# 6x7.net
KiCad netlist of a schematic drawn in EAGLE
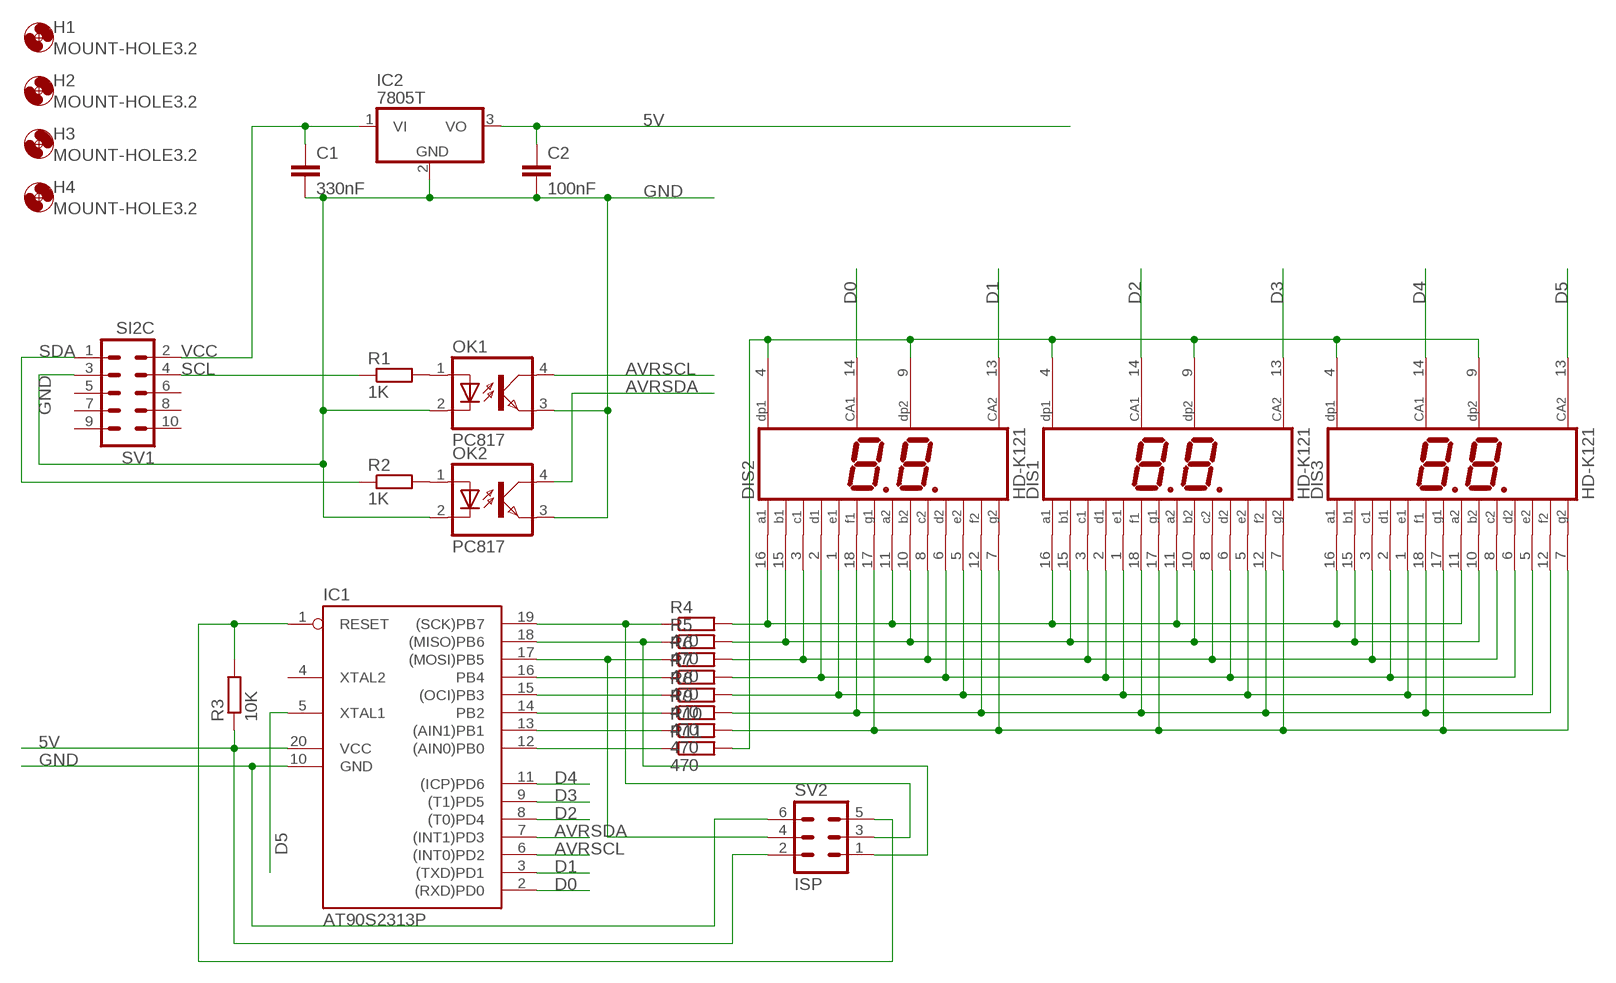
[diagram p0: schematic, sheet 1]

(export (version "E")
  (design (tool "Eeschema 10.0.6"))
  (components
    (comp (ref "C1")
      (value "330nF")
      (footprint "eagle-import:C2.5-3")
      (libsource (lib "eagle-import") (part "C2,5-3"))
    )
    (comp (ref "C2")
      (value "100nF")
      (footprint "eagle-import:C050-024X044")
      (libsource (lib "eagle-import") (part "C-EU050-024X044"))
    )
    (comp (ref "DIS1")
      (value "HD-K121")
      (footprint "eagle-import:HDSP-R")
      (libsource (lib "eagle-import") (part "HD-K121"))
    )
    (comp (ref "DIS2")
      (value "HD-K121")
      (footprint "eagle-import:HDSP-R")
      (libsource (lib "eagle-import") (part "HD-K121"))
    )
    (comp (ref "DIS3")
      (value "HD-K121")
      (footprint "eagle-import:HDSP-R")
      (libsource (lib "eagle-import") (part "HD-K121"))
    )
    (comp (ref "H1")
      (value "MOUNT-HOLE3.2")
      (footprint "eagle-import:3,2")
      (libsource (lib "eagle-import") (part "MOUNT-HOLE3.2"))
    )
    (comp (ref "H2")
      (value "MOUNT-HOLE3.2")
      (footprint "eagle-import:3,2")
      (libsource (lib "eagle-import") (part "MOUNT-HOLE3.2"))
    )
    (comp (ref "H3")
      (value "MOUNT-HOLE3.2")
      (footprint "eagle-import:3,2")
      (libsource (lib "eagle-import") (part "MOUNT-HOLE3.2"))
    )
    (comp (ref "H4")
      (value "MOUNT-HOLE3.2")
      (footprint "eagle-import:3,2")
      (libsource (lib "eagle-import") (part "MOUNT-HOLE3.2"))
    )
    (comp (ref "IC1")
      (value "AT90S2313P")
      (footprint "eagle-import:DIL20")
      (libsource (lib "eagle-import") (part "AT90S2313P"))
    )
    (comp (ref "IC2")
      (value "7805T")
      (footprint "eagle-import:TO220H")
      (libsource (lib "eagle-import") (part "78T05"))
    )
    (comp (ref "OK1")
      (value "PC817")
      (footprint "eagle-import:DIL04")
      (fields (field (name "MPN") "PC817X4J000F"))
      (libsource (lib "eagle-import") (part "PC817"))
    )
    (comp (ref "OK2")
      (value "PC817")
      (footprint "eagle-import:DIL04")
      (fields (field (name "MPN") "PC817X4J000F"))
      (libsource (lib "eagle-import") (part "PC817"))
    )
    (comp (ref "R1")
      (value "1K")
      (footprint "eagle-import:0207_10")
      (libsource (lib "eagle-import") (part "R-EU_0207/10"))
    )
    (comp (ref "R2")
      (value "1K")
      (footprint "eagle-import:0207_10")
      (libsource (lib "eagle-import") (part "R-EU_0207/10"))
    )
    (comp (ref "R3")
      (value "10K")
      (footprint "eagle-import:0207_10")
      (libsource (lib "eagle-import") (part "R-EU_0207/10"))
    )
    (comp (ref "R4")
      (value "470")
      (footprint "eagle-import:0207_10")
      (libsource (lib "eagle-import") (part "R-EU_0207/10"))
    )
    (comp (ref "R5")
      (value "470")
      (footprint "eagle-import:0207_10")
      (libsource (lib "eagle-import") (part "R-EU_0207/10"))
    )
    (comp (ref "R6")
      (value "470")
      (footprint "eagle-import:0207_10")
      (libsource (lib "eagle-import") (part "R-EU_0207/10"))
    )
    (comp (ref "R7")
      (value "470")
      (footprint "eagle-import:0207_10")
      (libsource (lib "eagle-import") (part "R-EU_0207/10"))
    )
    (comp (ref "R8")
      (value "470")
      (footprint "eagle-import:0207_10")
      (libsource (lib "eagle-import") (part "R-EU_0207/10"))
    )
    (comp (ref "R9")
      (value "470")
      (footprint "eagle-import:0207_10")
      (libsource (lib "eagle-import") (part "R-EU_0207/10"))
    )
    (comp (ref "R10")
      (value "470")
      (footprint "eagle-import:0207_10")
      (libsource (lib "eagle-import") (part "R-EU_0207/10"))
    )
    (comp (ref "R11")
      (value "470")
      (footprint "eagle-import:0207_10")
      (libsource (lib "eagle-import") (part "R-EU_0207/10"))
    )
    (comp (ref "SV1")
      (value "SI2C")
      (footprint "eagle-import:ML10")
      (libsource (lib "eagle-import") (part "ML10"))
    )
    (comp (ref "SV2")
      (value "ISP")
      (footprint "eagle-import:ML6")
      (libsource (lib "eagle-import") (part "ML6"))
    )
  )
  (nets
    (net (code "1") (name "/5V") (class "Default")
      (node (ref "C2") (pin "1") (pinfunction "1_1") (pintype "passive"))
      (node (ref "IC1") (pin "20") (pinfunction "VCC_20") (pintype "power_in"))
      (node (ref "IC2") (pin "3") (pinfunction "VO_3") (pintype "passive"))
      (node (ref "R3") (pin "1") (pinfunction "1_1") (pintype "passive"))
      (node (ref "SV2") (pin "2") (pinfunction "2_2") (pintype "passive"))
    )
    (net (code "2") (name "/AVRSCL") (class "Default")
      (node (ref "IC1") (pin "6") (pinfunction "(INT0)PD2_6") (pintype "bidirectional"))
      (node (ref "OK1") (pin "4") (pinfunction "COL_4") (pintype "passive"))
    )
    (net (code "3") (name "/AVRSDA") (class "Default")
      (node (ref "IC1") (pin "7") (pinfunction "(INT1)PD3_7") (pintype "bidirectional"))
      (node (ref "OK2") (pin "4") (pinfunction "COL_4") (pintype "passive"))
    )
    (net (code "4") (name "/D0") (class "Default")
      (node (ref "DIS2") (pin "14") (pinfunction "CA1_14") (pintype "passive"))
      (node (ref "IC1") (pin "2") (pinfunction "(RXD)PD0_2") (pintype "bidirectional"))
    )
    (net (code "5") (name "/D1") (class "Default")
      (node (ref "DIS2") (pin "13") (pinfunction "CA2_13") (pintype "passive"))
      (node (ref "IC1") (pin "3") (pinfunction "(TXD)PD1_3") (pintype "bidirectional"))
    )
    (net (code "6") (name "/D2") (class "Default")
      (node (ref "DIS1") (pin "14") (pinfunction "CA1_14") (pintype "passive"))
      (node (ref "IC1") (pin "8") (pinfunction "(T0)PD4_8") (pintype "bidirectional"))
    )
    (net (code "7") (name "/D3") (class "Default")
      (node (ref "DIS1") (pin "13") (pinfunction "CA2_13") (pintype "passive"))
      (node (ref "IC1") (pin "9") (pinfunction "(T1)PD5_9") (pintype "bidirectional"))
    )
    (net (code "8") (name "/D4") (class "Default")
      (node (ref "DIS3") (pin "14") (pinfunction "CA1_14") (pintype "passive"))
      (node (ref "IC1") (pin "11") (pinfunction "(ICP)PD6_11") (pintype "bidirectional"))
    )
    (net (code "9") (name "/D5") (class "Default")
      (node (ref "DIS3") (pin "13") (pinfunction "CA2_13") (pintype "passive"))
      (node (ref "IC1") (pin "5") (pinfunction "XTAL1_5") (pintype "bidirectional"))
    )
    (net (code "10") (name "/GND") (class "Default")
      (node (ref "C1") (pin "2") (pinfunction "2_2") (pintype "passive"))
      (node (ref "C2") (pin "2") (pinfunction "2_2") (pintype "passive"))
      (node (ref "IC1") (pin "10") (pinfunction "GND_10") (pintype "power_in"))
      (node (ref "IC2") (pin "2") (pinfunction "GND_2") (pintype "passive"))
      (node (ref "OK1") (pin "2") (pinfunction "C_2") (pintype "passive"))
      (node (ref "OK1") (pin "3") (pinfunction "EMIT_3") (pintype "passive"))
      (node (ref "OK2") (pin "2") (pinfunction "C_2") (pintype "passive"))
      (node (ref "OK2") (pin "3") (pinfunction "EMIT_3") (pintype "passive"))
      (node (ref "SV1") (pin "3") (pinfunction "3_3") (pintype "passive"))
      (node (ref "SV2") (pin "6") (pinfunction "6_6") (pintype "passive"))
    )
    (net (code "11") (name "/SCL") (class "Default")
      (node (ref "R1") (pin "1") (pinfunction "1_1") (pintype "passive"))
      (node (ref "SV1") (pin "4") (pinfunction "4_4") (pintype "passive"))
    )
    (net (code "12") (name "/SDA") (class "Default")
      (node (ref "R2") (pin "1") (pinfunction "1_1") (pintype "passive"))
      (node (ref "SV1") (pin "1") (pinfunction "1_1") (pintype "passive"))
    )
    (net (code "13") (name "/VCC") (class "Default")
      (node (ref "C1") (pin "1") (pinfunction "1_1") (pintype "passive"))
      (node (ref "IC2") (pin "1") (pinfunction "VI_1") (pintype "input"))
      (node (ref "SV1") (pin "2") (pinfunction "2_2") (pintype "passive"))
    )
    (net (code "14") (name "Net-(DIS1-A1)") (class "Default")
      (node (ref "DIS1") (pin "11") (pinfunction "A2_11") (pintype "passive"))
      (node (ref "DIS1") (pin "16") (pinfunction "A1_16") (pintype "passive"))
      (node (ref "DIS2") (pin "11") (pinfunction "A2_11") (pintype "passive"))
      (node (ref "DIS2") (pin "16") (pinfunction "A1_16") (pintype "passive"))
      (node (ref "DIS3") (pin "11") (pinfunction "A2_11") (pintype "passive"))
      (node (ref "DIS3") (pin "16") (pinfunction "A1_16") (pintype "passive"))
      (node (ref "R4") (pin "2") (pinfunction "2_2") (pintype "passive"))
    )
    (net (code "15") (name "Net-(DIS1-B1)") (class "Default")
      (node (ref "DIS1") (pin "10") (pinfunction "B2_10") (pintype "passive"))
      (node (ref "DIS1") (pin "15") (pinfunction "B1_15") (pintype "passive"))
      (node (ref "DIS2") (pin "10") (pinfunction "B2_10") (pintype "passive"))
      (node (ref "DIS2") (pin "15") (pinfunction "B1_15") (pintype "passive"))
      (node (ref "DIS3") (pin "10") (pinfunction "B2_10") (pintype "passive"))
      (node (ref "DIS3") (pin "15") (pinfunction "B1_15") (pintype "passive"))
      (node (ref "R5") (pin "2") (pinfunction "2_2") (pintype "passive"))
    )
    (net (code "16") (name "Net-(DIS1-C1)") (class "Default")
      (node (ref "DIS1") (pin "3") (pinfunction "C1_3") (pintype "passive"))
      (node (ref "DIS1") (pin "8") (pinfunction "C2_8") (pintype "passive"))
      (node (ref "DIS2") (pin "3") (pinfunction "C1_3") (pintype "passive"))
      (node (ref "DIS2") (pin "8") (pinfunction "C2_8") (pintype "passive"))
      (node (ref "DIS3") (pin "3") (pinfunction "C1_3") (pintype "passive"))
      (node (ref "DIS3") (pin "8") (pinfunction "C2_8") (pintype "passive"))
      (node (ref "R6") (pin "2") (pinfunction "2_2") (pintype "passive"))
    )
    (net (code "17") (name "Net-(DIS1-D1)") (class "Default")
      (node (ref "DIS1") (pin "2") (pinfunction "D1_2") (pintype "passive"))
      (node (ref "DIS1") (pin "6") (pinfunction "D2_6") (pintype "passive"))
      (node (ref "DIS2") (pin "2") (pinfunction "D1_2") (pintype "passive"))
      (node (ref "DIS2") (pin "6") (pinfunction "D2_6") (pintype "passive"))
      (node (ref "DIS3") (pin "2") (pinfunction "D1_2") (pintype "passive"))
      (node (ref "DIS3") (pin "6") (pinfunction "D2_6") (pintype "passive"))
      (node (ref "R7") (pin "2") (pinfunction "2_2") (pintype "passive"))
    )
    (net (code "18") (name "Net-(DIS1-DP1)") (class "Default")
      (node (ref "DIS1") (pin "4") (pinfunction "DP1_4") (pintype "passive"))
      (node (ref "DIS1") (pin "9") (pinfunction "DP2_9") (pintype "passive"))
      (node (ref "DIS2") (pin "4") (pinfunction "DP1_4") (pintype "passive"))
      (node (ref "DIS2") (pin "9") (pinfunction "DP2_9") (pintype "passive"))
      (node (ref "DIS3") (pin "4") (pinfunction "DP1_4") (pintype "passive"))
      (node (ref "DIS3") (pin "9") (pinfunction "DP2_9") (pintype "passive"))
      (node (ref "R11") (pin "2") (pinfunction "2_2") (pintype "passive"))
    )
    (net (code "19") (name "Net-(DIS1-E1)") (class "Default")
      (node (ref "DIS1") (pin "1") (pinfunction "E1_1") (pintype "passive"))
      (node (ref "DIS1") (pin "5") (pinfunction "E2_5") (pintype "passive"))
      (node (ref "DIS2") (pin "1") (pinfunction "E1_1") (pintype "passive"))
      (node (ref "DIS2") (pin "5") (pinfunction "E2_5") (pintype "passive"))
      (node (ref "DIS3") (pin "1") (pinfunction "E1_1") (pintype "passive"))
      (node (ref "DIS3") (pin "5") (pinfunction "E2_5") (pintype "passive"))
      (node (ref "R8") (pin "2") (pinfunction "2_2") (pintype "passive"))
    )
    (net (code "20") (name "Net-(DIS1-F1)") (class "Default")
      (node (ref "DIS1") (pin "12") (pinfunction "F2_12") (pintype "passive"))
      (node (ref "DIS1") (pin "18") (pinfunction "F1_18") (pintype "passive"))
      (node (ref "DIS2") (pin "12") (pinfunction "F2_12") (pintype "passive"))
      (node (ref "DIS2") (pin "18") (pinfunction "F1_18") (pintype "passive"))
      (node (ref "DIS3") (pin "12") (pinfunction "F2_12") (pintype "passive"))
      (node (ref "DIS3") (pin "18") (pinfunction "F1_18") (pintype "passive"))
      (node (ref "R9") (pin "2") (pinfunction "2_2") (pintype "passive"))
    )
    (net (code "21") (name "Net-(DIS1-G1)") (class "Default")
      (node (ref "DIS1") (pin "17") (pinfunction "G1_17") (pintype "passive"))
      (node (ref "DIS1") (pin "7") (pinfunction "G2_7") (pintype "passive"))
      (node (ref "DIS2") (pin "17") (pinfunction "G1_17") (pintype "passive"))
      (node (ref "DIS2") (pin "7") (pinfunction "G2_7") (pintype "passive"))
      (node (ref "DIS3") (pin "17") (pinfunction "G1_17") (pintype "passive"))
      (node (ref "DIS3") (pin "7") (pinfunction "G2_7") (pintype "passive"))
      (node (ref "R10") (pin "2") (pinfunction "2_2") (pintype "passive"))
    )
    (net (code "22") (name "Net-(IC1-(AIN0)PB0)") (class "Default")
      (node (ref "IC1") (pin "12") (pinfunction "(AIN0)PB0_12") (pintype "bidirectional"))
      (node (ref "R11") (pin "1") (pinfunction "1_1") (pintype "passive"))
    )
    (net (code "23") (name "Net-(IC1-(AIN1)PB1)") (class "Default")
      (node (ref "IC1") (pin "13") (pinfunction "(AIN1)PB1_13") (pintype "bidirectional"))
      (node (ref "R10") (pin "1") (pinfunction "1_1") (pintype "passive"))
    )
    (net (code "24") (name "Net-(IC1-(MISO)PB6)") (class "Default")
      (node (ref "IC1") (pin "18") (pinfunction "(MISO)PB6_18") (pintype "bidirectional"))
      (node (ref "R5") (pin "1") (pinfunction "1_1") (pintype "passive"))
      (node (ref "SV2") (pin "1") (pinfunction "1_1") (pintype "passive"))
    )
    (net (code "25") (name "Net-(IC1-(MOSI)PB5)") (class "Default")
      (node (ref "IC1") (pin "17") (pinfunction "(MOSI)PB5_17") (pintype "bidirectional"))
      (node (ref "R6") (pin "1") (pinfunction "1_1") (pintype "passive"))
      (node (ref "SV2") (pin "4") (pinfunction "4_4") (pintype "passive"))
    )
    (net (code "26") (name "Net-(IC1-(OCI)PB3)") (class "Default")
      (node (ref "IC1") (pin "15") (pinfunction "(OCI)PB3_15") (pintype "bidirectional"))
      (node (ref "R8") (pin "1") (pinfunction "1_1") (pintype "passive"))
    )
    (net (code "27") (name "Net-(IC1-(SCK)PB7)") (class "Default")
      (node (ref "IC1") (pin "19") (pinfunction "(SCK)PB7_19") (pintype "bidirectional"))
      (node (ref "R4") (pin "1") (pinfunction "1_1") (pintype "passive"))
      (node (ref "SV2") (pin "3") (pinfunction "3_3") (pintype "passive"))
    )
    (net (code "28") (name "Net-(IC1-PB2)") (class "Default")
      (node (ref "IC1") (pin "14") (pinfunction "PB2_14") (pintype "bidirectional"))
      (node (ref "R9") (pin "1") (pinfunction "1_1") (pintype "passive"))
    )
    (net (code "29") (name "Net-(IC1-PB4)") (class "Default")
      (node (ref "IC1") (pin "16") (pinfunction "PB4_16") (pintype "bidirectional"))
      (node (ref "R7") (pin "1") (pinfunction "1_1") (pintype "passive"))
    )
    (net (code "30") (name "Net-(IC1-RESET)") (class "Default")
      (node (ref "IC1") (pin "1") (pinfunction "RESET_1") (pintype "bidirectional"))
      (node (ref "R3") (pin "2") (pinfunction "2_2") (pintype "passive"))
      (node (ref "SV2") (pin "5") (pinfunction "5_5") (pintype "passive"))
    )
    (net (code "31") (name "Net-(OK1-A)") (class "Default")
      (node (ref "OK1") (pin "1") (pinfunction "A_1") (pintype "passive"))
      (node (ref "R1") (pin "2") (pinfunction "2_2") (pintype "passive"))
    )
    (net (code "32") (name "Net-(OK2-A)") (class "Default")
      (node (ref "OK2") (pin "1") (pinfunction "A_1") (pintype "passive"))
      (node (ref "R2") (pin "2") (pinfunction "2_2") (pintype "passive"))
    )
    (net (code "33") (name "unconnected-(IC1-XTAL2-Pad4)") (class "Default")
      (node (ref "IC1") (pin "4") (pinfunction "XTAL2_4") (pintype "bidirectional"))
    )
    (net (code "34") (name "unconnected-(SV1-Pad5)") (class "Default")
      (node (ref "SV1") (pin "5") (pinfunction "5_5") (pintype "passive"))
    )
    (net (code "35") (name "unconnected-(SV1-Pad6)") (class "Default")
      (node (ref "SV1") (pin "6") (pinfunction "6_6") (pintype "passive"))
    )
    (net (code "36") (name "unconnected-(SV1-Pad7)") (class "Default")
      (node (ref "SV1") (pin "7") (pinfunction "7_7") (pintype "passive"))
    )
    (net (code "37") (name "unconnected-(SV1-Pad8)") (class "Default")
      (node (ref "SV1") (pin "8") (pinfunction "8_8") (pintype "passive"))
    )
    (net (code "38") (name "unconnected-(SV1-Pad9)") (class "Default")
      (node (ref "SV1") (pin "9") (pinfunction "9_9") (pintype "passive"))
    )
    (net (code "39") (name "unconnected-(SV1-Pad10)") (class "Default")
      (node (ref "SV1") (pin "10") (pinfunction "10_10") (pintype "passive"))
    )
  )
)
